# riffle-proto-0_1.net
KiCad netlist of a schematic drawn in EAGLE
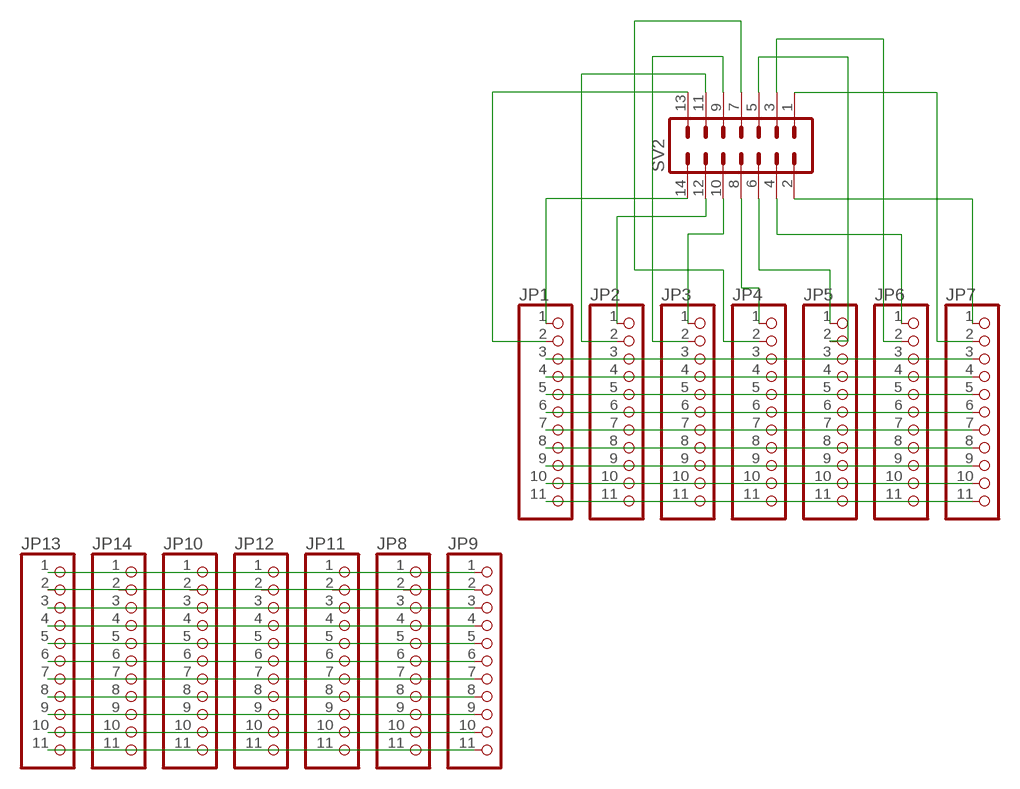
[diagram p0: schematic, sheet 1]

(export (version "E")
  (design (tool "Eeschema 10.0.6"))
  (components
    (comp (ref "JP1")
      (value "HEADER-1X1176MIL")
      (footprint "eagle-import:1X11_ROUND_76")
      (libsource (lib "eagle-import") (part "HEADER-1X1176MIL"))
    )
    (comp (ref "JP2")
      (value "HEADER-1X1176MIL")
      (footprint "eagle-import:1X11_ROUND_76")
      (libsource (lib "eagle-import") (part "HEADER-1X1176MIL"))
    )
    (comp (ref "JP3")
      (value "HEADER-1X1176MIL")
      (footprint "eagle-import:1X11_ROUND_76")
      (libsource (lib "eagle-import") (part "HEADER-1X1176MIL"))
    )
    (comp (ref "JP4")
      (value "HEADER-1X1176MIL")
      (footprint "eagle-import:1X11_ROUND_76")
      (libsource (lib "eagle-import") (part "HEADER-1X1176MIL"))
    )
    (comp (ref "JP5")
      (value "HEADER-1X1176MIL")
      (footprint "eagle-import:1X11_ROUND_76")
      (libsource (lib "eagle-import") (part "HEADER-1X1176MIL"))
    )
    (comp (ref "JP6")
      (value "HEADER-1X1176MIL")
      (footprint "eagle-import:1X11_ROUND_76")
      (libsource (lib "eagle-import") (part "HEADER-1X1176MIL"))
    )
    (comp (ref "JP7")
      (value "HEADER-1X1176MIL")
      (footprint "eagle-import:1X11_ROUND_76")
      (libsource (lib "eagle-import") (part "HEADER-1X1176MIL"))
    )
    (comp (ref "JP8")
      (value "HEADER-1X1176MIL")
      (footprint "eagle-import:1X11_ROUND_76")
      (libsource (lib "eagle-import") (part "HEADER-1X1176MIL"))
    )
    (comp (ref "JP9")
      (value "HEADER-1X1176MIL")
      (footprint "eagle-import:1X11_ROUND_76")
      (libsource (lib "eagle-import") (part "HEADER-1X1176MIL"))
    )
    (comp (ref "JP10")
      (value "HEADER-1X1176MIL")
      (footprint "eagle-import:1X11_ROUND_76")
      (libsource (lib "eagle-import") (part "HEADER-1X1176MIL"))
    )
    (comp (ref "JP11")
      (value "HEADER-1X1176MIL")
      (footprint "eagle-import:1X11_ROUND_76")
      (libsource (lib "eagle-import") (part "HEADER-1X1176MIL"))
    )
    (comp (ref "JP12")
      (value "HEADER-1X1176MIL")
      (footprint "eagle-import:1X11_ROUND_76")
      (libsource (lib "eagle-import") (part "HEADER-1X1176MIL"))
    )
    (comp (ref "JP13")
      (value "HEADER-1X1176MIL")
      (footprint "eagle-import:1X11_ROUND_76")
      (libsource (lib "eagle-import") (part "HEADER-1X1176MIL"))
    )
    (comp (ref "JP14")
      (value "HEADER-1X1176MIL")
      (footprint "eagle-import:1X11_ROUND_76")
      (libsource (lib "eagle-import") (part "HEADER-1X1176MIL"))
    )
    (comp (ref "SV2")
      (value "MA07-2")
      (footprint "eagle-import:MA07-2")
      (libsource (lib "eagle-import") (part "MA07-2"))
    )
  )
  (nets
    (net (code "1") (name "Net-(JP1-Pad1)") (class "Default")
      (node (ref "JP1") (pin "1") (pinfunction "1_1") (pintype "passive"))
      (node (ref "SV2") (pin "14") (pinfunction "14_14") (pintype "passive"))
    )
    (net (code "2") (name "Net-(JP1-Pad2)") (class "Default")
      (node (ref "JP1") (pin "2") (pinfunction "2_2") (pintype "passive"))
      (node (ref "SV2") (pin "13") (pinfunction "13_13") (pintype "passive"))
    )
    (net (code "3") (name "Net-(JP1-Pad3)") (class "Default")
      (node (ref "JP1") (pin "3") (pinfunction "3_3") (pintype "passive"))
      (node (ref "JP2") (pin "3") (pinfunction "3_3") (pintype "passive"))
      (node (ref "JP3") (pin "3") (pinfunction "3_3") (pintype "passive"))
      (node (ref "JP4") (pin "3") (pinfunction "3_3") (pintype "passive"))
      (node (ref "JP5") (pin "3") (pinfunction "3_3") (pintype "passive"))
      (node (ref "JP6") (pin "3") (pinfunction "3_3") (pintype "passive"))
      (node (ref "JP7") (pin "3") (pinfunction "3_3") (pintype "passive"))
    )
    (net (code "4") (name "Net-(JP1-Pad4)") (class "Default")
      (node (ref "JP1") (pin "4") (pinfunction "4_4") (pintype "passive"))
      (node (ref "JP2") (pin "4") (pinfunction "4_4") (pintype "passive"))
      (node (ref "JP3") (pin "4") (pinfunction "4_4") (pintype "passive"))
      (node (ref "JP4") (pin "4") (pinfunction "4_4") (pintype "passive"))
      (node (ref "JP5") (pin "4") (pinfunction "4_4") (pintype "passive"))
      (node (ref "JP6") (pin "4") (pinfunction "4_4") (pintype "passive"))
      (node (ref "JP7") (pin "4") (pinfunction "4_4") (pintype "passive"))
    )
    (net (code "5") (name "Net-(JP1-Pad5)") (class "Default")
      (node (ref "JP1") (pin "5") (pinfunction "5_5") (pintype "passive"))
      (node (ref "JP2") (pin "5") (pinfunction "5_5") (pintype "passive"))
      (node (ref "JP3") (pin "5") (pinfunction "5_5") (pintype "passive"))
      (node (ref "JP4") (pin "5") (pinfunction "5_5") (pintype "passive"))
      (node (ref "JP5") (pin "5") (pinfunction "5_5") (pintype "passive"))
      (node (ref "JP6") (pin "5") (pinfunction "5_5") (pintype "passive"))
      (node (ref "JP7") (pin "5") (pinfunction "5_5") (pintype "passive"))
    )
    (net (code "6") (name "Net-(JP1-Pad6)") (class "Default")
      (node (ref "JP1") (pin "6") (pinfunction "6_6") (pintype "passive"))
      (node (ref "JP2") (pin "6") (pinfunction "6_6") (pintype "passive"))
      (node (ref "JP3") (pin "6") (pinfunction "6_6") (pintype "passive"))
      (node (ref "JP4") (pin "6") (pinfunction "6_6") (pintype "passive"))
      (node (ref "JP5") (pin "6") (pinfunction "6_6") (pintype "passive"))
      (node (ref "JP6") (pin "6") (pinfunction "6_6") (pintype "passive"))
      (node (ref "JP7") (pin "6") (pinfunction "6_6") (pintype "passive"))
    )
    (net (code "7") (name "Net-(JP1-Pad7)") (class "Default")
      (node (ref "JP1") (pin "7") (pinfunction "7_7") (pintype "passive"))
      (node (ref "JP2") (pin "7") (pinfunction "7_7") (pintype "passive"))
      (node (ref "JP3") (pin "7") (pinfunction "7_7") (pintype "passive"))
      (node (ref "JP4") (pin "7") (pinfunction "7_7") (pintype "passive"))
      (node (ref "JP5") (pin "7") (pinfunction "7_7") (pintype "passive"))
      (node (ref "JP6") (pin "7") (pinfunction "7_7") (pintype "passive"))
      (node (ref "JP7") (pin "7") (pinfunction "7_7") (pintype "passive"))
    )
    (net (code "8") (name "Net-(JP1-Pad8)") (class "Default")
      (node (ref "JP1") (pin "8") (pinfunction "8_8") (pintype "passive"))
      (node (ref "JP2") (pin "8") (pinfunction "8_8") (pintype "passive"))
      (node (ref "JP3") (pin "8") (pinfunction "8_8") (pintype "passive"))
      (node (ref "JP4") (pin "8") (pinfunction "8_8") (pintype "passive"))
      (node (ref "JP5") (pin "8") (pinfunction "8_8") (pintype "passive"))
      (node (ref "JP6") (pin "8") (pinfunction "8_8") (pintype "passive"))
      (node (ref "JP7") (pin "8") (pinfunction "8_8") (pintype "passive"))
    )
    (net (code "9") (name "Net-(JP1-Pad9)") (class "Default")
      (node (ref "JP1") (pin "9") (pinfunction "9_9") (pintype "passive"))
      (node (ref "JP2") (pin "9") (pinfunction "9_9") (pintype "passive"))
      (node (ref "JP3") (pin "9") (pinfunction "9_9") (pintype "passive"))
      (node (ref "JP4") (pin "9") (pinfunction "9_9") (pintype "passive"))
      (node (ref "JP5") (pin "9") (pinfunction "9_9") (pintype "passive"))
      (node (ref "JP6") (pin "9") (pinfunction "9_9") (pintype "passive"))
      (node (ref "JP7") (pin "9") (pinfunction "9_9") (pintype "passive"))
    )
    (net (code "10") (name "Net-(JP1-Pad10)") (class "Default")
      (node (ref "JP1") (pin "10") (pinfunction "10_10") (pintype "passive"))
      (node (ref "JP2") (pin "10") (pinfunction "10_10") (pintype "passive"))
      (node (ref "JP3") (pin "10") (pinfunction "10_10") (pintype "passive"))
      (node (ref "JP4") (pin "10") (pinfunction "10_10") (pintype "passive"))
      (node (ref "JP5") (pin "10") (pinfunction "10_10") (pintype "passive"))
      (node (ref "JP6") (pin "10") (pinfunction "10_10") (pintype "passive"))
      (node (ref "JP7") (pin "10") (pinfunction "10_10") (pintype "passive"))
    )
    (net (code "11") (name "Net-(JP1-Pad11)") (class "Default")
      (node (ref "JP1") (pin "11") (pinfunction "11_11") (pintype "passive"))
      (node (ref "JP2") (pin "11") (pinfunction "11_11") (pintype "passive"))
      (node (ref "JP4") (pin "11") (pinfunction "11_11") (pintype "passive"))
      (node (ref "JP5") (pin "11") (pinfunction "11_11") (pintype "passive"))
      (node (ref "JP6") (pin "11") (pinfunction "11_11") (pintype "passive"))
      (node (ref "JP7") (pin "11") (pinfunction "11_11") (pintype "passive"))
    )
    (net (code "12") (name "Net-(JP2-Pad1)") (class "Default")
      (node (ref "JP2") (pin "1") (pinfunction "1_1") (pintype "passive"))
      (node (ref "SV2") (pin "12") (pinfunction "12_12") (pintype "passive"))
    )
    (net (code "13") (name "Net-(JP2-Pad2)") (class "Default")
      (node (ref "JP2") (pin "2") (pinfunction "2_2") (pintype "passive"))
      (node (ref "SV2") (pin "11") (pinfunction "11_11") (pintype "passive"))
    )
    (net (code "14") (name "Net-(JP3-Pad1)") (class "Default")
      (node (ref "JP3") (pin "1") (pinfunction "1_1") (pintype "passive"))
      (node (ref "SV2") (pin "10") (pinfunction "10_10") (pintype "passive"))
    )
    (net (code "15") (name "Net-(JP3-Pad2)") (class "Default")
      (node (ref "JP3") (pin "2") (pinfunction "2_2") (pintype "passive"))
      (node (ref "SV2") (pin "9") (pinfunction "9_9") (pintype "passive"))
    )
    (net (code "16") (name "Net-(JP4-Pad1)") (class "Default")
      (node (ref "JP4") (pin "1") (pinfunction "1_1") (pintype "passive"))
      (node (ref "SV2") (pin "8") (pinfunction "8_8") (pintype "passive"))
    )
    (net (code "17") (name "Net-(JP4-Pad2)") (class "Default")
      (node (ref "JP4") (pin "2") (pinfunction "2_2") (pintype "passive"))
      (node (ref "SV2") (pin "7") (pinfunction "7_7") (pintype "passive"))
    )
    (net (code "18") (name "Net-(JP5-Pad1)") (class "Default")
      (node (ref "JP5") (pin "1") (pinfunction "1_1") (pintype "passive"))
      (node (ref "SV2") (pin "6") (pinfunction "6_6") (pintype "passive"))
    )
    (net (code "19") (name "Net-(JP5-Pad2)") (class "Default")
      (node (ref "JP5") (pin "2") (pinfunction "2_2") (pintype "passive"))
      (node (ref "SV2") (pin "5") (pinfunction "5_5") (pintype "passive"))
    )
    (net (code "20") (name "Net-(JP6-Pad1)") (class "Default")
      (node (ref "JP6") (pin "1") (pinfunction "1_1") (pintype "passive"))
      (node (ref "SV2") (pin "4") (pinfunction "4_4") (pintype "passive"))
    )
    (net (code "21") (name "Net-(JP6-Pad2)") (class "Default")
      (node (ref "JP6") (pin "2") (pinfunction "2_2") (pintype "passive"))
      (node (ref "SV2") (pin "3") (pinfunction "3_3") (pintype "passive"))
    )
    (net (code "22") (name "Net-(JP7-Pad1)") (class "Default")
      (node (ref "JP7") (pin "1") (pinfunction "1_1") (pintype "passive"))
      (node (ref "SV2") (pin "2") (pinfunction "2_2") (pintype "passive"))
    )
    (net (code "23") (name "Net-(JP7-Pad2)") (class "Default")
      (node (ref "JP7") (pin "2") (pinfunction "2_2") (pintype "passive"))
      (node (ref "SV2") (pin "1") (pinfunction "1_1") (pintype "passive"))
    )
    (net (code "24") (name "Net-(JP10-Pad1)") (class "Default")
      (node (ref "JP10") (pin "1") (pinfunction "1_1") (pintype "passive"))
      (node (ref "JP11") (pin "1") (pinfunction "1_1") (pintype "passive"))
      (node (ref "JP12") (pin "1") (pinfunction "1_1") (pintype "passive"))
      (node (ref "JP13") (pin "1") (pinfunction "1_1") (pintype "passive"))
      (node (ref "JP14") (pin "1") (pinfunction "1_1") (pintype "passive"))
      (node (ref "JP8") (pin "1") (pinfunction "1_1") (pintype "passive"))
      (node (ref "JP9") (pin "1") (pinfunction "1_1") (pintype "passive"))
    )
    (net (code "25") (name "Net-(JP10-Pad2)") (class "Default")
      (node (ref "JP10") (pin "2") (pinfunction "2_2") (pintype "passive"))
      (node (ref "JP11") (pin "2") (pinfunction "2_2") (pintype "passive"))
      (node (ref "JP12") (pin "2") (pinfunction "2_2") (pintype "passive"))
      (node (ref "JP13") (pin "2") (pinfunction "2_2") (pintype "passive"))
      (node (ref "JP14") (pin "2") (pinfunction "2_2") (pintype "passive"))
      (node (ref "JP8") (pin "2") (pinfunction "2_2") (pintype "passive"))
      (node (ref "JP9") (pin "2") (pinfunction "2_2") (pintype "passive"))
    )
    (net (code "26") (name "Net-(JP10-Pad3)") (class "Default")
      (node (ref "JP10") (pin "3") (pinfunction "3_3") (pintype "passive"))
      (node (ref "JP11") (pin "3") (pinfunction "3_3") (pintype "passive"))
      (node (ref "JP12") (pin "3") (pinfunction "3_3") (pintype "passive"))
      (node (ref "JP13") (pin "3") (pinfunction "3_3") (pintype "passive"))
      (node (ref "JP14") (pin "3") (pinfunction "3_3") (pintype "passive"))
      (node (ref "JP8") (pin "3") (pinfunction "3_3") (pintype "passive"))
      (node (ref "JP9") (pin "3") (pinfunction "3_3") (pintype "passive"))
    )
    (net (code "27") (name "Net-(JP10-Pad4)") (class "Default")
      (node (ref "JP10") (pin "4") (pinfunction "4_4") (pintype "passive"))
      (node (ref "JP11") (pin "4") (pinfunction "4_4") (pintype "passive"))
      (node (ref "JP12") (pin "4") (pinfunction "4_4") (pintype "passive"))
      (node (ref "JP13") (pin "4") (pinfunction "4_4") (pintype "passive"))
      (node (ref "JP14") (pin "4") (pinfunction "4_4") (pintype "passive"))
      (node (ref "JP8") (pin "4") (pinfunction "4_4") (pintype "passive"))
      (node (ref "JP9") (pin "4") (pinfunction "4_4") (pintype "passive"))
    )
    (net (code "28") (name "Net-(JP10-Pad5)") (class "Default")
      (node (ref "JP10") (pin "5") (pinfunction "5_5") (pintype "passive"))
      (node (ref "JP11") (pin "5") (pinfunction "5_5") (pintype "passive"))
      (node (ref "JP12") (pin "5") (pinfunction "5_5") (pintype "passive"))
      (node (ref "JP13") (pin "5") (pinfunction "5_5") (pintype "passive"))
      (node (ref "JP14") (pin "5") (pinfunction "5_5") (pintype "passive"))
      (node (ref "JP8") (pin "5") (pinfunction "5_5") (pintype "passive"))
      (node (ref "JP9") (pin "5") (pinfunction "5_5") (pintype "passive"))
    )
    (net (code "29") (name "Net-(JP10-Pad6)") (class "Default")
      (node (ref "JP10") (pin "6") (pinfunction "6_6") (pintype "passive"))
      (node (ref "JP11") (pin "6") (pinfunction "6_6") (pintype "passive"))
      (node (ref "JP12") (pin "6") (pinfunction "6_6") (pintype "passive"))
      (node (ref "JP13") (pin "6") (pinfunction "6_6") (pintype "passive"))
      (node (ref "JP14") (pin "6") (pinfunction "6_6") (pintype "passive"))
      (node (ref "JP8") (pin "6") (pinfunction "6_6") (pintype "passive"))
      (node (ref "JP9") (pin "6") (pinfunction "6_6") (pintype "passive"))
    )
    (net (code "30") (name "Net-(JP10-Pad7)") (class "Default")
      (node (ref "JP10") (pin "7") (pinfunction "7_7") (pintype "passive"))
      (node (ref "JP11") (pin "7") (pinfunction "7_7") (pintype "passive"))
      (node (ref "JP12") (pin "7") (pinfunction "7_7") (pintype "passive"))
      (node (ref "JP13") (pin "7") (pinfunction "7_7") (pintype "passive"))
      (node (ref "JP14") (pin "7") (pinfunction "7_7") (pintype "passive"))
      (node (ref "JP8") (pin "7") (pinfunction "7_7") (pintype "passive"))
      (node (ref "JP9") (pin "7") (pinfunction "7_7") (pintype "passive"))
    )
    (net (code "31") (name "Net-(JP10-Pad8)") (class "Default")
      (node (ref "JP10") (pin "8") (pinfunction "8_8") (pintype "passive"))
      (node (ref "JP11") (pin "8") (pinfunction "8_8") (pintype "passive"))
      (node (ref "JP12") (pin "8") (pinfunction "8_8") (pintype "passive"))
      (node (ref "JP13") (pin "8") (pinfunction "8_8") (pintype "passive"))
      (node (ref "JP14") (pin "8") (pinfunction "8_8") (pintype "passive"))
      (node (ref "JP8") (pin "8") (pinfunction "8_8") (pintype "passive"))
      (node (ref "JP9") (pin "8") (pinfunction "8_8") (pintype "passive"))
    )
    (net (code "32") (name "Net-(JP10-Pad9)") (class "Default")
      (node (ref "JP10") (pin "9") (pinfunction "9_9") (pintype "passive"))
      (node (ref "JP11") (pin "9") (pinfunction "9_9") (pintype "passive"))
      (node (ref "JP12") (pin "9") (pinfunction "9_9") (pintype "passive"))
      (node (ref "JP13") (pin "9") (pinfunction "9_9") (pintype "passive"))
      (node (ref "JP14") (pin "9") (pinfunction "9_9") (pintype "passive"))
      (node (ref "JP8") (pin "9") (pinfunction "9_9") (pintype "passive"))
      (node (ref "JP9") (pin "9") (pinfunction "9_9") (pintype "passive"))
    )
    (net (code "33") (name "Net-(JP10-Pad10)") (class "Default")
      (node (ref "JP10") (pin "10") (pinfunction "10_10") (pintype "passive"))
      (node (ref "JP11") (pin "10") (pinfunction "10_10") (pintype "passive"))
      (node (ref "JP12") (pin "10") (pinfunction "10_10") (pintype "passive"))
      (node (ref "JP13") (pin "10") (pinfunction "10_10") (pintype "passive"))
      (node (ref "JP14") (pin "10") (pinfunction "10_10") (pintype "passive"))
      (node (ref "JP8") (pin "10") (pinfunction "10_10") (pintype "passive"))
      (node (ref "JP9") (pin "10") (pinfunction "10_10") (pintype "passive"))
    )
    (net (code "34") (name "Net-(JP11-Pad11)") (class "Default")
      (node (ref "JP11") (pin "11") (pinfunction "11_11") (pintype "passive"))
      (node (ref "JP12") (pin "11") (pinfunction "11_11") (pintype "passive"))
      (node (ref "JP13") (pin "11") (pinfunction "11_11") (pintype "passive"))
      (node (ref "JP14") (pin "11") (pinfunction "11_11") (pintype "passive"))
      (node (ref "JP8") (pin "11") (pinfunction "11_11") (pintype "passive"))
      (node (ref "JP9") (pin "11") (pinfunction "11_11") (pintype "passive"))
    )
    (net (code "35") (name "unconnected-(JP3-Pad11)") (class "Default")
      (node (ref "JP3") (pin "11") (pinfunction "11_11") (pintype "passive"))
    )
    (net (code "36") (name "unconnected-(JP10-Pad11)") (class "Default")
      (node (ref "JP10") (pin "11") (pinfunction "11_11") (pintype "passive"))
    )
  )
)
